# relay.net
KiCad netlist of a schematic drawn in EAGLE
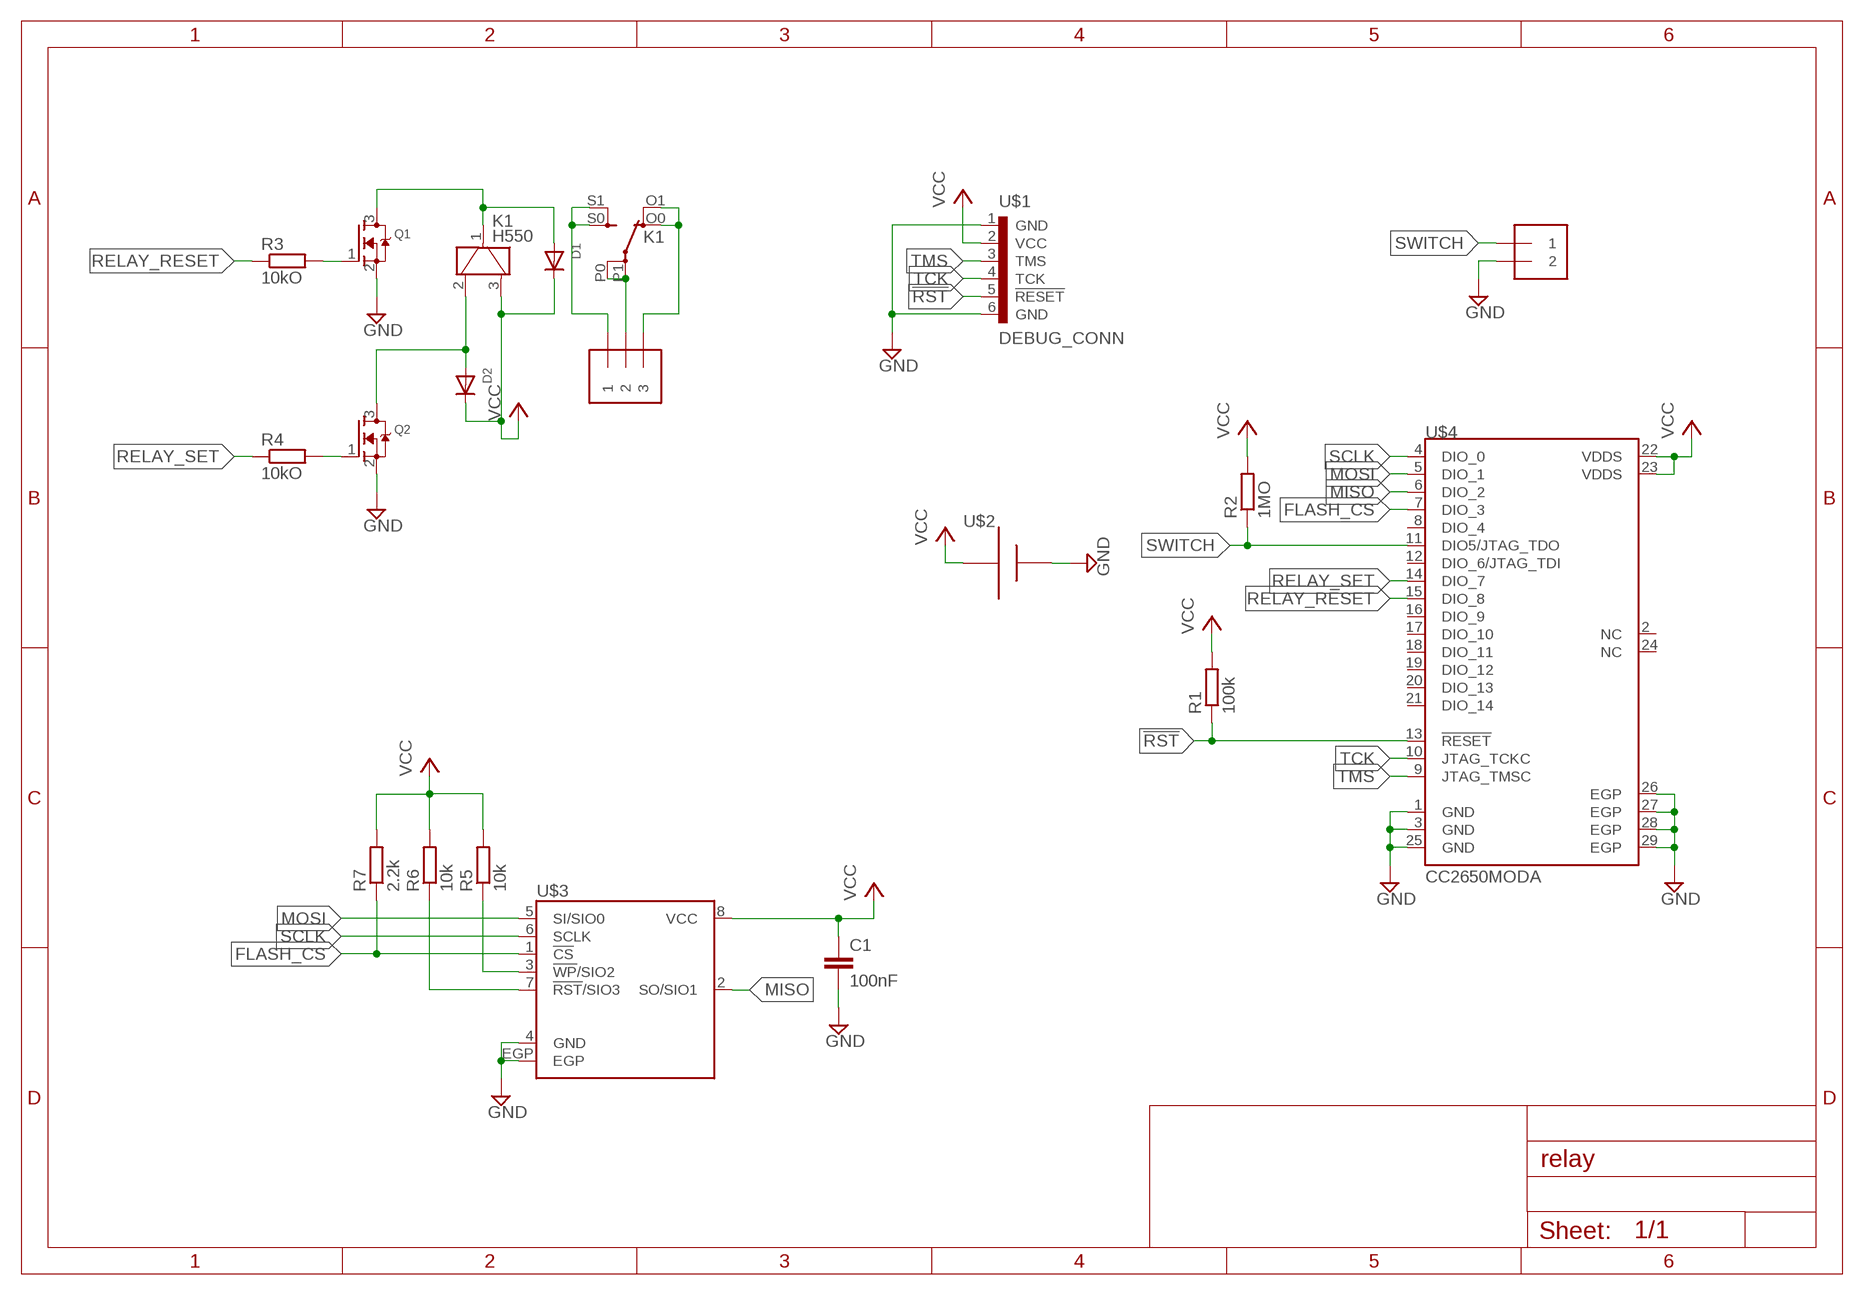
[diagram p0: schematic, sheet 1]

(export (version "E")
  (design (tool "Eeschema 10.0.6"))
  (components
    (comp (ref "C1")
      (value "100nF")
      (footprint "eagle-import:0402")
      (libsource (lib "eagle-import") (part "CAPACITOR_0402"))
    )
    (comp (ref "D1")
      (value "DIODESOD-123")
      (footprint "eagle-import:SOD-123")
      (libsource (lib "eagle-import") (part "DIODESOD-123"))
    )
    (comp (ref "D2")
      (value "DIODESOD-123")
      (footprint "eagle-import:SOD-123")
      (libsource (lib "eagle-import") (part "DIODESOD-123"))
    )
    (comp (ref "J1")
      (value "1X3-5MM")
      (footprint "eagle-import:1X3-5MM")
      (libsource (lib "eagle-import") (part "1X3-5MM"))
    )
    (comp (ref "J2")
      (value "1X2-3.5MM")
      (footprint "eagle-import:1X2-3.5MM")
      (libsource (lib "eagle-import") (part "1X2-3.5MM"))
    )
    (comp (ref "K1")
      (value "H550")
      (footprint "eagle-import:H550")
      (libsource (lib "eagle-import") (part "H550"))
    )
    (comp (ref "Q1")
      (value "MOSFET-NREFLOW")
      (footprint "eagle-import:SOT23")
      (libsource (lib "eagle-import") (part "MOSFET-NREFLOW"))
    )
    (comp (ref "Q2")
      (value "MOSFET-NREFLOW")
      (footprint "eagle-import:SOT23")
      (libsource (lib "eagle-import") (part "MOSFET-NREFLOW"))
    )
    (comp (ref "R1")
      (value "100k")
      (footprint "eagle-import:0402")
      (libsource (lib "eagle-import") (part "RESISTOR_0402"))
    )
    (comp (ref "R2")
      (value "1MO")
      (footprint "eagle-import:0402")
      (libsource (lib "eagle-import") (part "RESISTOR_0402"))
    )
    (comp (ref "R3")
      (value "10kO")
      (footprint "eagle-import:0402")
      (libsource (lib "eagle-import") (part "RESISTOR_0402"))
    )
    (comp (ref "R4")
      (value "10kO")
      (footprint "eagle-import:0402")
      (libsource (lib "eagle-import") (part "RESISTOR_0402"))
    )
    (comp (ref "R5")
      (value "10k")
      (footprint "eagle-import:0402")
      (libsource (lib "eagle-import") (part "RESISTOR_0402"))
    )
    (comp (ref "R6")
      (value "10k")
      (footprint "eagle-import:0402")
      (libsource (lib "eagle-import") (part "RESISTOR_0402"))
    )
    (comp (ref "R7")
      (value "2.2k")
      (footprint "eagle-import:0402")
      (libsource (lib "eagle-import") (part "RESISTOR_0402"))
    )
    (comp (ref "U$1")
      (value "DEBUG_CONN")
      (footprint "eagle-import:DEBUG_CONN")
      (libsource (lib "eagle-import") (part "DEBUG_CONN"))
    )
    (comp (ref "U$2")
      (value "CR2_SPRINGS")
      (footprint "eagle-import:CR2")
      (libsource (lib "eagle-import") (part "CR2_SPRINGS"))
    )
    (comp (ref "U$3")
      (value "MX25R8035FMX25R8035FZUIL0")
      (footprint "eagle-import:MX25R8035FZUIL0")
      (libsource (lib "eagle-import") (part "MX25R8035FMX25R8035FZUIL0"))
    )
    (comp (ref "U$4")
      (value "CC2650MODA")
      (footprint "eagle-import:CC2650MODA")
      (libsource (lib "eagle-import") (part "CC2650MODA"))
    )
  )
  (nets
    (net (code "1") (name "/~{RST}") (class "Default")
      (node (ref "R1") (pin "1") (pinfunction "1_1") (pintype "passive"))
      (node (ref "U$1") (pin "5") (pinfunction "~{RESET}_5") (pintype "bidirectional"))
      (node (ref "U$4") (pin "13") (pinfunction "~{RESET}_13") (pintype "bidirectional"))
    )
    (net (code "2") (name "FLASH_CS") (class "Default")
      (node (ref "R7") (pin "1") (pinfunction "1_1") (pintype "passive"))
      (node (ref "U$3") (pin "1") (pinfunction "~{CS}_1") (pintype "input"))
      (node (ref "U$4") (pin "7") (pinfunction "DIO_3_7") (pintype "bidirectional"))
    )
    (net (code "3") (name "GND") (class "Default")
      (node (ref "C1") (pin "2") (pinfunction "2_2") (pintype "passive"))
      (node (ref "J2") (pin "2") (pinfunction "2_2") (pintype "passive"))
      (node (ref "Q1") (pin "2") (pinfunction "S_2") (pintype "bidirectional"))
      (node (ref "Q2") (pin "2") (pinfunction "S_2") (pintype "bidirectional"))
      (node (ref "U$1") (pin "1") (pinfunction "GND_1") (pintype "bidirectional"))
      (node (ref "U$1") (pin "6") (pinfunction "GND_6") (pintype "bidirectional"))
      (node (ref "U$2") (pin "-") (pinfunction "-_-") (pintype "bidirectional"))
      (node (ref "U$2") (pin "-@1") (pinfunction "-_-@1") (pintype "bidirectional"))
      (node (ref "U$2") (pin "-@2") (pinfunction "-_-@2") (pintype "bidirectional"))
      (node (ref "U$2") (pin "-@3") (pinfunction "-_-@3") (pintype "bidirectional"))
      (node (ref "U$3") (pin "4") (pinfunction "GND_4") (pintype "power_in"))
      (node (ref "U$3") (pin "EGP") (pinfunction "EGP_EGP") (pintype "power_in"))
      (node (ref "U$4") (pin "1") (pinfunction "GND_1") (pintype "power_in"))
      (node (ref "U$4") (pin "25") (pinfunction "GND_25") (pintype "power_in"))
      (node (ref "U$4") (pin "26") (pinfunction "EGP_26") (pintype "power_in"))
      (node (ref "U$4") (pin "27") (pinfunction "EGP_27") (pintype "power_in"))
      (node (ref "U$4") (pin "28") (pinfunction "EGP_28") (pintype "power_in"))
      (node (ref "U$4") (pin "29") (pinfunction "EGP_29") (pintype "power_in"))
      (node (ref "U$4") (pin "3") (pinfunction "GND_3") (pintype "power_in"))
    )
    (net (code "4") (name "MISO") (class "Default")
      (node (ref "U$3") (pin "2") (pinfunction "SO/SIO1_2") (pintype "bidirectional"))
      (node (ref "U$4") (pin "6") (pinfunction "DIO_2_6") (pintype "bidirectional"))
    )
    (net (code "5") (name "MOSI") (class "Default")
      (node (ref "U$3") (pin "5") (pinfunction "SI/SIO0_5") (pintype "bidirectional"))
      (node (ref "U$4") (pin "5") (pinfunction "DIO_1_5") (pintype "bidirectional"))
    )
    (net (code "6") (name "Net-(J1-Pad1)") (class "Default")
      (node (ref "J1") (pin "1") (pinfunction "1_1") (pintype "passive"))
      (node (ref "K1") (pin "S0") (pinfunction "S_S0") (pintype "passive"))
      (node (ref "K1") (pin "S1") (pinfunction "S_S1") (pintype "passive"))
    )
    (net (code "7") (name "Net-(J1-Pad2)") (class "Default")
      (node (ref "J1") (pin "2") (pinfunction "2_2") (pintype "passive"))
      (node (ref "K1") (pin "P0") (pinfunction "P_P0") (pintype "passive"))
      (node (ref "K1") (pin "P1") (pinfunction "P_P1") (pintype "passive"))
    )
    (net (code "8") (name "Net-(J1-Pad3)") (class "Default")
      (node (ref "J1") (pin "3") (pinfunction "3_3") (pintype "passive"))
      (node (ref "K1") (pin "O0") (pinfunction "O_O0") (pintype "passive"))
      (node (ref "K1") (pin "O1") (pinfunction "O_O1") (pintype "passive"))
    )
    (net (code "9") (name "Net-(Q1-D)") (class "Default")
      (node (ref "D1") (pin "A") (pinfunction "A_A") (pintype "passive"))
      (node (ref "K1") (pin "1") (pinfunction "1_1") (pintype "passive"))
      (node (ref "Q1") (pin "3") (pinfunction "D_3") (pintype "bidirectional"))
    )
    (net (code "10") (name "Net-(Q1-G)") (class "Default")
      (node (ref "Q1") (pin "1") (pinfunction "G_1") (pintype "bidirectional"))
      (node (ref "R3") (pin "2") (pinfunction "2_2") (pintype "passive"))
    )
    (net (code "11") (name "Net-(Q2-D)") (class "Default")
      (node (ref "D2") (pin "A") (pinfunction "A_A") (pintype "passive"))
      (node (ref "K1") (pin "2") (pinfunction "2_2") (pintype "passive"))
      (node (ref "Q2") (pin "3") (pinfunction "D_3") (pintype "bidirectional"))
    )
    (net (code "12") (name "Net-(Q2-G)") (class "Default")
      (node (ref "Q2") (pin "1") (pinfunction "G_1") (pintype "bidirectional"))
      (node (ref "R4") (pin "2") (pinfunction "2_2") (pintype "passive"))
    )
    (net (code "13") (name "Net-(U$3-~{RST}{slash}SIO3)") (class "Default")
      (node (ref "R6") (pin "1") (pinfunction "1_1") (pintype "passive"))
      (node (ref "U$3") (pin "7") (pinfunction "~{RST}/SIO3_7") (pintype "bidirectional"))
    )
    (net (code "14") (name "Net-(U$3-~{WP}{slash}SIO2)") (class "Default")
      (node (ref "R5") (pin "1") (pinfunction "1_1") (pintype "passive"))
      (node (ref "U$3") (pin "3") (pinfunction "~{WP}/SIO2_3") (pintype "bidirectional"))
    )
    (net (code "15") (name "RELAY_RESET") (class "Default")
      (node (ref "R3") (pin "1") (pinfunction "1_1") (pintype "passive"))
      (node (ref "U$4") (pin "15") (pinfunction "DIO_8_15") (pintype "bidirectional"))
    )
    (net (code "16") (name "RELAY_SET") (class "Default")
      (node (ref "R4") (pin "1") (pinfunction "1_1") (pintype "passive"))
      (node (ref "U$4") (pin "14") (pinfunction "DIO_7_14") (pintype "bidirectional"))
    )
    (net (code "17") (name "SCLK") (class "Default")
      (node (ref "U$3") (pin "6") (pinfunction "SCLK_6") (pintype "input"))
      (node (ref "U$4") (pin "4") (pinfunction "DIO_0_4") (pintype "bidirectional"))
    )
    (net (code "18") (name "SWITCH") (class "Default")
      (node (ref "J2") (pin "1") (pinfunction "1_1") (pintype "passive"))
      (node (ref "R2") (pin "1") (pinfunction "1_1") (pintype "passive"))
      (node (ref "U$4") (pin "11") (pinfunction "DIO5/JTAG_TDO_11") (pintype "bidirectional"))
    )
    (net (code "19") (name "TCK") (class "Default")
      (node (ref "U$1") (pin "4") (pinfunction "TCK_4") (pintype "bidirectional"))
      (node (ref "U$4") (pin "10") (pinfunction "JTAG_TCKC_10") (pintype "bidirectional"))
    )
    (net (code "20") (name "TMS") (class "Default")
      (node (ref "U$1") (pin "3") (pinfunction "TMS_3") (pintype "bidirectional"))
      (node (ref "U$4") (pin "9") (pinfunction "JTAG_TMSC_9") (pintype "bidirectional"))
    )
    (net (code "21") (name "VCC") (class "Default")
      (node (ref "C1") (pin "1") (pinfunction "1_1") (pintype "passive"))
      (node (ref "D1") (pin "C") (pinfunction "C_C") (pintype "passive"))
      (node (ref "D2") (pin "C") (pinfunction "C_C") (pintype "passive"))
      (node (ref "K1") (pin "3") (pinfunction "3_3") (pintype "passive"))
      (node (ref "R1") (pin "2") (pinfunction "2_2") (pintype "passive"))
      (node (ref "R2") (pin "2") (pinfunction "2_2") (pintype "passive"))
      (node (ref "R5") (pin "2") (pinfunction "2_2") (pintype "passive"))
      (node (ref "R6") (pin "2") (pinfunction "2_2") (pintype "passive"))
      (node (ref "R7") (pin "2") (pinfunction "2_2") (pintype "passive"))
      (node (ref "U$1") (pin "2") (pinfunction "VCC_2") (pintype "bidirectional"))
      (node (ref "U$2") (pin "+") (pinfunction "+_+") (pintype "bidirectional"))
      (node (ref "U$2") (pin "+@1") (pinfunction "+_+@1") (pintype "bidirectional"))
      (node (ref "U$2") (pin "+@2") (pinfunction "+_+@2") (pintype "bidirectional"))
      (node (ref "U$2") (pin "+@3") (pinfunction "+_+@3") (pintype "bidirectional"))
      (node (ref "U$3") (pin "8") (pinfunction "VCC_8") (pintype "power_in"))
      (node (ref "U$4") (pin "22") (pinfunction "VDDS_22") (pintype "power_in"))
      (node (ref "U$4") (pin "23") (pinfunction "VDDS_23") (pintype "power_in"))
    )
    (net (code "22") (name "unconnected-(U$4-DIO_4-Pad8)") (class "Default")
      (node (ref "U$4") (pin "8") (pinfunction "DIO_4_8") (pintype "bidirectional"))
    )
    (net (code "23") (name "unconnected-(U$4-DIO_6{slash}JTAG_TDI-Pad12)") (class "Default")
      (node (ref "U$4") (pin "12") (pinfunction "DIO_6/JTAG_TDI_12") (pintype "bidirectional"))
    )
    (net (code "24") (name "unconnected-(U$4-DIO_9-Pad16)") (class "Default")
      (node (ref "U$4") (pin "16") (pinfunction "DIO_9_16") (pintype "bidirectional"))
    )
    (net (code "25") (name "unconnected-(U$4-DIO_10-Pad17)") (class "Default")
      (node (ref "U$4") (pin "17") (pinfunction "DIO_10_17") (pintype "bidirectional"))
    )
    (net (code "26") (name "unconnected-(U$4-DIO_11-Pad18)") (class "Default")
      (node (ref "U$4") (pin "18") (pinfunction "DIO_11_18") (pintype "bidirectional"))
    )
    (net (code "27") (name "unconnected-(U$4-DIO_12-Pad19)") (class "Default")
      (node (ref "U$4") (pin "19") (pinfunction "DIO_12_19") (pintype "bidirectional"))
    )
    (net (code "28") (name "unconnected-(U$4-DIO_13-Pad20)") (class "Default")
      (node (ref "U$4") (pin "20") (pinfunction "DIO_13_20") (pintype "bidirectional"))
    )
    (net (code "29") (name "unconnected-(U$4-DIO_14-Pad21)") (class "Default")
      (node (ref "U$4") (pin "21") (pinfunction "DIO_14_21") (pintype "bidirectional"))
    )
    (net (code "30") (name "unconnected-(U$4-NC-Pad2)") (class "Default")
      (node (ref "U$4") (pin "2") (pinfunction "NC_2") (pintype "no_connect"))
    )
    (net (code "31") (name "unconnected-(U$4-NC-Pad24)") (class "Default")
      (node (ref "U$4") (pin "24") (pinfunction "NC_24") (pintype "no_connect"))
    )
  )
)
